# TLM_002_SD.net
KiCad netlist of a schematic drawn in Altium Designer
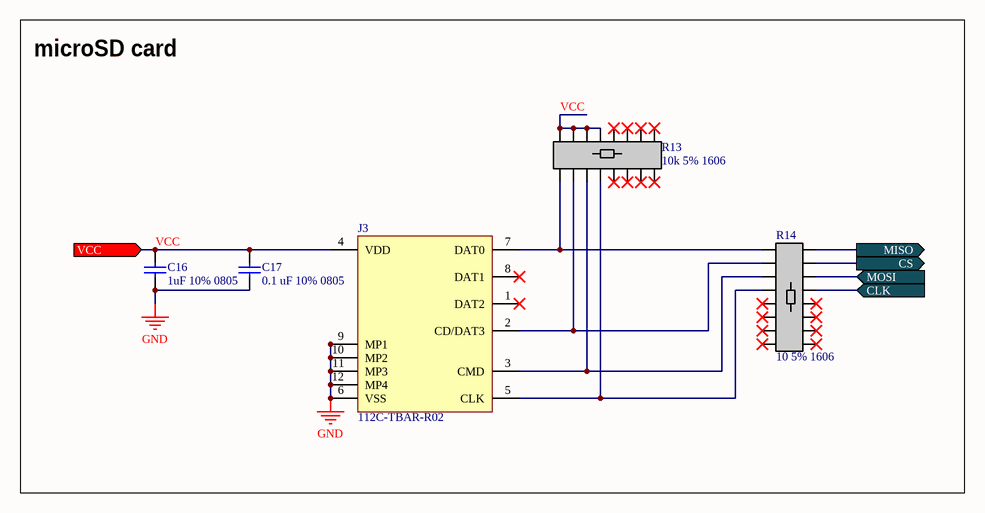
[diagram p0: TLM_002_SD.SchDoc]

(export (version "E")
  (design (tool "Eeschema 10.0.6"))
  (components
    (comp (ref "C16")
      (value "1uF 10% 0805")
      (footprint "CAPC2013X145X50NL20T20")
      (fields (field (name "PART NUMBER") "VJ0805Y105KXQRW1BC") (field (name "MANUFACTURER") "Vitramon"))
      (libsource (lib "Altium Content Vault") (part "CAP"))
    )
    (comp (ref "C17")
      (value "0.1 uF 10% 0805")
      (footprint "CAPC2013X140X50ML20T25")
      (fields
        (field (name "PART NUMBER") "0805DD104KAT2A")
        (field (name "MANUFACTURER") "AVX Interconnect / Elco")
      )
      (libsource (lib "Altium Content Vault") (part "CAP"))
    )
    (comp (ref "J3")
      (value "112C-TBAR-R02")
      (footprint "SamacSys:112CTBARR02")
      (description "Connector")
      (libsource (lib "SamacSys") (part "112C-TBAR-R02"))
    )
    (comp (ref "R13")
      (value "10k 5% 1606")
      (footprint "RES Array")
      (libsource (lib "Generic-Schematic-Library") (part "RES_ARRAY_10k"))
    )
    (comp (ref "R14")
      (value "10 5% 1606")
      (footprint "RES Array")
      (libsource (lib "Generic-Schematic-Library") (part "RES_ARRAY_10"))
    )
  )
  (nets
    (net (code "1") (name "/CLK") (class "Default")
      (node (ref "R14") (pin "13") (pinfunction "13_13") (pintype "passive"))
    )
    (net (code "2") (name "/CS") (class "Default")
      (node (ref "R14") (pin "15") (pinfunction "15_15") (pintype "passive"))
    )
    (net (code "3") (name "/MISO") (class "Default")
      (node (ref "R14") (pin "16") (pinfunction "16_16") (pintype "passive"))
    )
    (net (code "4") (name "/MOSI") (class "Default")
      (node (ref "R14") (pin "14") (pinfunction "14_14") (pintype "passive"))
    )
    (net (code "5") (name "/VCC") (class "Default")
      (node (ref "C16") (pin "2") (pinfunction "2_2") (pintype "passive"))
      (node (ref "C17") (pin "2") (pinfunction "2_2") (pintype "passive"))
      (node (ref "J3") (pin "4") (pinfunction "VDD_4") (pintype "passive"))
      (node (ref "R13") (pin "13") (pinfunction "13_13") (pintype "passive"))
      (node (ref "R13") (pin "14") (pinfunction "14_14") (pintype "passive"))
      (node (ref "R13") (pin "15") (pinfunction "15_15") (pintype "passive"))
      (node (ref "R13") (pin "16") (pinfunction "16_16") (pintype "passive"))
    )
    (net (code "6") (name "GND") (class "Default")
      (node (ref "C16") (pin "1") (pinfunction "1_1") (pintype "passive"))
      (node (ref "C17") (pin "1") (pinfunction "1_1") (pintype "passive"))
      (node (ref "J3") (pin "10") (pinfunction "MP2_10") (pintype "passive"))
      (node (ref "J3") (pin "11") (pinfunction "MP3_11") (pintype "passive"))
      (node (ref "J3") (pin "12") (pinfunction "MP4_12") (pintype "passive"))
      (node (ref "J3") (pin "6") (pinfunction "VSS_6") (pintype "passive"))
      (node (ref "J3") (pin "9") (pinfunction "MP1_9") (pintype "passive"))
    )
    (net (code "7") (name "Net-(J3-CD{slash}DAT3)") (class "Default")
      (node (ref "J3") (pin "2") (pinfunction "CD/DAT3_2") (pintype "passive"))
      (node (ref "R13") (pin "2") (pinfunction "2_2") (pintype "passive"))
      (node (ref "R14") (pin "2") (pinfunction "2_2") (pintype "passive"))
    )
    (net (code "8") (name "Net-(J3-CLK)") (class "Default")
      (node (ref "J3") (pin "5") (pinfunction "CLK_5") (pintype "passive"))
      (node (ref "R13") (pin "4") (pinfunction "4_4") (pintype "passive"))
      (node (ref "R14") (pin "4") (pinfunction "4_4") (pintype "passive"))
    )
    (net (code "9") (name "Net-(J3-CMD)") (class "Default")
      (node (ref "J3") (pin "3") (pinfunction "CMD_3") (pintype "passive"))
      (node (ref "R13") (pin "3") (pinfunction "3_3") (pintype "passive"))
      (node (ref "R14") (pin "3") (pinfunction "3_3") (pintype "passive"))
    )
    (net (code "10") (name "Net-(J3-DAT0)") (class "Default")
      (node (ref "J3") (pin "7") (pinfunction "DAT0_7") (pintype "passive"))
      (node (ref "R13") (pin "1") (pinfunction "1_1") (pintype "passive"))
      (node (ref "R14") (pin "1") (pinfunction "1_1") (pintype "passive"))
    )
    (net (code "11") (name "unconnected-(J3-DAT1-Pad8)") (class "Default")
      (node (ref "J3") (pin "8") (pinfunction "DAT1_8") (pintype "passive+no_connect"))
    )
    (net (code "12") (name "unconnected-(J3-DAT2-Pad1)") (class "Default")
      (node (ref "J3") (pin "1") (pinfunction "DAT2_1") (pintype "passive+no_connect"))
    )
    (net (code "13") (name "unconnected-(R13-Pad5)") (class "Default")
      (node (ref "R13") (pin "5") (pinfunction "5_5") (pintype "passive+no_connect"))
    )
    (net (code "14") (name "unconnected-(R13-Pad6)") (class "Default")
      (node (ref "R13") (pin "6") (pinfunction "6_6") (pintype "passive+no_connect"))
    )
    (net (code "15") (name "unconnected-(R13-Pad7)") (class "Default")
      (node (ref "R13") (pin "7") (pinfunction "7_7") (pintype "passive+no_connect"))
    )
    (net (code "16") (name "unconnected-(R13-Pad8)") (class "Default")
      (node (ref "R13") (pin "8") (pinfunction "8_8") (pintype "passive+no_connect"))
    )
    (net (code "17") (name "unconnected-(R13-Pad9)") (class "Default")
      (node (ref "R13") (pin "9") (pinfunction "9_9") (pintype "passive+no_connect"))
    )
    (net (code "18") (name "unconnected-(R13-Pad10)") (class "Default")
      (node (ref "R13") (pin "10") (pinfunction "10_10") (pintype "passive+no_connect"))
    )
    (net (code "19") (name "unconnected-(R13-Pad11)") (class "Default")
      (node (ref "R13") (pin "11") (pinfunction "11_11") (pintype "passive+no_connect"))
    )
    (net (code "20") (name "unconnected-(R13-Pad12)") (class "Default")
      (node (ref "R13") (pin "12") (pinfunction "12_12") (pintype "passive+no_connect"))
    )
    (net (code "21") (name "unconnected-(R14-Pad5)") (class "Default")
      (node (ref "R14") (pin "5") (pinfunction "5_5") (pintype "passive+no_connect"))
    )
    (net (code "22") (name "unconnected-(R14-Pad6)") (class "Default")
      (node (ref "R14") (pin "6") (pinfunction "6_6") (pintype "passive+no_connect"))
    )
    (net (code "23") (name "unconnected-(R14-Pad7)") (class "Default")
      (node (ref "R14") (pin "7") (pinfunction "7_7") (pintype "passive+no_connect"))
    )
    (net (code "24") (name "unconnected-(R14-Pad8)") (class "Default")
      (node (ref "R14") (pin "8") (pinfunction "8_8") (pintype "passive+no_connect"))
    )
    (net (code "25") (name "unconnected-(R14-Pad9)") (class "Default")
      (node (ref "R14") (pin "9") (pinfunction "9_9") (pintype "passive+no_connect"))
    )
    (net (code "26") (name "unconnected-(R14-Pad10)") (class "Default")
      (node (ref "R14") (pin "10") (pinfunction "10_10") (pintype "passive+no_connect"))
    )
    (net (code "27") (name "unconnected-(R14-Pad11)") (class "Default")
      (node (ref "R14") (pin "11") (pinfunction "11_11") (pintype "passive+no_connect"))
    )
    (net (code "28") (name "unconnected-(R14-Pad12)") (class "Default")
      (node (ref "R14") (pin "12") (pinfunction "12_12") (pintype "passive+no_connect"))
    )
  )
)
